# Navigator_Connectors.net
KiCad netlist of a schematic drawn in Altium Designer
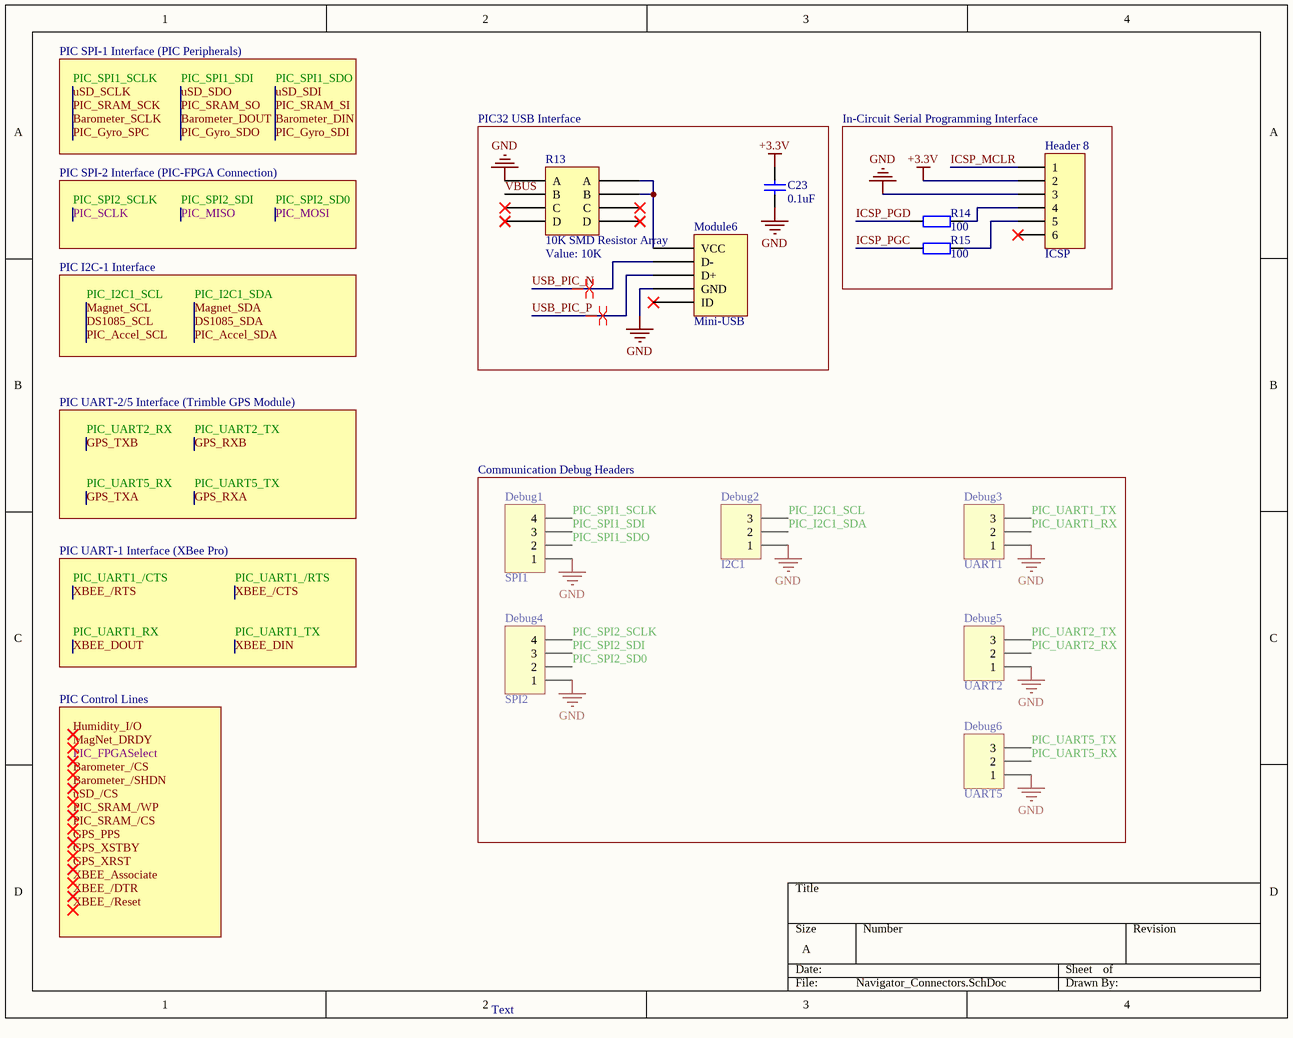
[diagram p0: Navigator_Connectors.SchDoc]

(export (version "E")
  (design (tool "Eeschema 10.0.6"))
  (components
    (comp (ref "C23")
      (value "0.1uF")
      (footprint "SMD 1206")
      (description "Capacitor")
      (fields (field (name "Comment") "0.1uF SMD 1206"))
      (libsource (lib "Miscellaneous Devices") (part "Cap"))
    )
    (comp (ref "Debug1")
      (value "SPI1")
      (footprint "HDR1X4")
      (description "Header, 4-Pin")
      (fields (field (name "PUBLISHER") "Altium Limited"))
      (libsource (lib "Miscellaneous Connectors") (part "Header 4"))
    )
    (comp (ref "Debug2")
      (value "I2C1")
      (footprint "HDR1X3")
      (description "Header, 3-Pin")
      (fields (field (name "PUBLISHER") "Altium Limited"))
      (libsource (lib "Miscellaneous Connectors") (part "Header 3"))
    )
    (comp (ref "Debug3")
      (value "UART1")
      (footprint "HDR1X3")
      (description "Header, 3-Pin")
      (fields (field (name "PUBLISHER") "Altium Limited"))
      (libsource (lib "Miscellaneous Connectors") (part "Header 3"))
    )
    (comp (ref "Debug4")
      (value "SPI2")
      (footprint "HDR1X4")
      (description "Header, 4-Pin")
      (fields (field (name "PUBLISHER") "Altium Limited"))
      (libsource (lib "Miscellaneous Connectors") (part "Header 4"))
    )
    (comp (ref "Debug5")
      (value "UART2")
      (footprint "HDR1X3")
      (description "Header, 3-Pin")
      (fields (field (name "PUBLISHER") "Altium Limited"))
      (libsource (lib "Miscellaneous Connectors") (part "Header 3"))
    )
    (comp (ref "Debug6")
      (value "UART5")
      (footprint "HDR1X3")
      (description "Header, 3-Pin")
      (fields (field (name "PUBLISHER") "Altium Limited"))
      (libsource (lib "Miscellaneous Connectors") (part "Header 3"))
    )
    (comp (ref "Header 8")
      (value "ICSP")
      (footprint "HDR1X6H")
      (description "Header, 6-Pin")
      (fields (field (name "PUBLISHER") "Altium Limited"))
      (libsource (lib "Miscellaneous Connectors") (part "Header 6"))
    )
    (comp (ref "Module6")
      (value "Mini-USB")
      (footprint "Mini B USB Connector")
      (libsource (lib "Ad-Flier_Parts") (part "Mini USB Connector"))
    )
    (comp (ref "R13")
      (value "10K SMD Resistor Array")
      (footprint "Resistor Array YC164")
      (description "4-Count Resistor Array")
      (fields (field (name "ALTIUM_VALUE") "10K"))
      (libsource (lib "Ad-Flier_Parts") (part "SMD Resistor Array"))
    )
    (comp (ref "R14")
      (value "100")
      (footprint "SMD 0805")
      (description "Resistor")
      (fields (field (name "Comment") "100 SMD 0805"))
      (libsource (lib "Miscellaneous Devices") (part "Res2"))
    )
    (comp (ref "R15")
      (value "100")
      (footprint "SMD 0805")
      (description "Resistor")
      (fields (field (name "Comment") "100 SMD 0805"))
      (libsource (lib "Miscellaneous Devices") (part "Res2"))
    )
  )
  (nets
    (net (code "1") (name "+3.3V") (class "Default")
      (node (ref "C23") (pin "2") (pinfunction "2_2") (pintype "passive"))
      (node (ref "Header 8") (pin "2") (pinfunction "2_2") (pintype "passive"))
    )
    (net (code "2") (name "/Barometer_DIN") (class "Default")
      (node (ref "Debug1") (pin "2") (pinfunction "2_2") (pintype "passive"))
    )
    (net (code "3") (name "/Barometer_DOUT") (class "Default")
      (node (ref "Debug1") (pin "3") (pinfunction "3_3") (pintype "passive"))
    )
    (net (code "4") (name "/Barometer_SCLK") (class "Default")
      (node (ref "Debug1") (pin "4") (pinfunction "4_4") (pintype "passive"))
    )
    (net (code "7") (name "/DS1085_SCL") (class "Default")
      (node (ref "Debug2") (pin "3") (pinfunction "3_3") (pintype "passive"))
    )
    (net (code "8") (name "/DS1085_SDA") (class "Default")
      (node (ref "Debug2") (pin "2") (pinfunction "2_2") (pintype "passive"))
    )
    (net (code "10") (name "/GPS_RXA") (class "Default")
      (node (ref "Debug6") (pin "3") (pinfunction "3_3") (pintype "passive"))
    )
    (net (code "11") (name "/GPS_RXB") (class "Default")
      (node (ref "Debug5") (pin "3") (pinfunction "3_3") (pintype "passive"))
    )
    (net (code "12") (name "/GPS_TXA") (class "Default")
      (node (ref "Debug6") (pin "2") (pinfunction "2_2") (pintype "passive"))
    )
    (net (code "13") (name "/GPS_TXB") (class "Default")
      (node (ref "Debug5") (pin "2") (pinfunction "2_2") (pintype "passive"))
    )
    (net (code "17") (name "/ICSP_MCLR") (class "Default")
      (node (ref "Header 8") (pin "1") (pinfunction "1_1") (pintype "passive"))
    )
    (net (code "18") (name "/ICSP_PGC") (class "Default")
      (node (ref "R15") (pin "2") (pinfunction "2_2") (pintype "passive"))
    )
    (net (code "19") (name "/ICSP_PGD") (class "Default")
      (node (ref "R14") (pin "2") (pinfunction "2_2") (pintype "passive"))
    )
    (net (code "22") (name "/PIC_MISO") (class "Default")
      (node (ref "Debug4") (pin "3") (pinfunction "3_3") (pintype "passive"))
    )
    (net (code "23") (name "/PIC_MOSI") (class "Default")
      (node (ref "Debug4") (pin "2") (pinfunction "2_2") (pintype "passive"))
    )
    (net (code "24") (name "/PIC_SCLK") (class "Default")
      (node (ref "Debug4") (pin "4") (pinfunction "4_4") (pintype "passive"))
    )
    (net (code "27") (name "/PIC_UART1_RX") (class "Default")
      (node (ref "Debug3") (pin "2") (pinfunction "2_2") (pintype "passive"))
    )
    (net (code "28") (name "/PIC_UART1_TX") (class "Default")
      (node (ref "Debug3") (pin "3") (pinfunction "3_3") (pintype "passive"))
    )
    (net (code "31") (name "/USB_PIC_N") (class "Default")
      (node (ref "Module6") (pin "3") (pinfunction "D-_3") (pintype "passive"))
    )
    (net (code "32") (name "/USB_PIC_P") (class "Default")
      (node (ref "Module6") (pin "2") (pinfunction "D+_2") (pintype "passive"))
    )
    (net (code "33") (name "/VBUS") (class "Default")
      (node (ref "R13") (pin "6") (pinfunction "B_6") (pintype "passive"))
    )
    (net (code "38") (name "GND") (class "Default")
      (node (ref "C23") (pin "1") (pinfunction "1_1") (pintype "passive"))
      (node (ref "Debug1") (pin "1") (pinfunction "1_1") (pintype "passive"))
      (node (ref "Debug2") (pin "1") (pinfunction "1_1") (pintype "passive"))
      (node (ref "Debug3") (pin "1") (pinfunction "1_1") (pintype "passive"))
      (node (ref "Debug4") (pin "1") (pinfunction "1_1") (pintype "passive"))
      (node (ref "Debug5") (pin "1") (pinfunction "1_1") (pintype "passive"))
      (node (ref "Debug6") (pin "1") (pinfunction "1_1") (pintype "passive"))
      (node (ref "Header 8") (pin "3") (pinfunction "3_3") (pintype "passive"))
      (node (ref "Module6") (pin "0") (pinfunction "GND_0") (pintype "passive"))
      (node (ref "R13") (pin "5") (pinfunction "A_5") (pintype "passive"))
    )
    (net (code "39") (name "Net-(Header 8-Pad4)") (class "Default")
      (node (ref "Header 8") (pin "4") (pinfunction "4_4") (pintype "passive"))
      (node (ref "R14") (pin "1") (pinfunction "1_1") (pintype "passive"))
    )
    (net (code "40") (name "Net-(Header 8-Pad5)") (class "Default")
      (node (ref "Header 8") (pin "5") (pinfunction "5_5") (pintype "passive"))
      (node (ref "R15") (pin "1") (pinfunction "1_1") (pintype "passive"))
    )
    (net (code "41") (name "Net-(Module6-VCC)") (class "Default")
      (node (ref "Module6") (pin "4") (pinfunction "VCC_4") (pintype "passive"))
      (node (ref "R13") (pin "1") (pinfunction "A_1") (pintype "passive"))
      (node (ref "R13") (pin "2") (pinfunction "B_2") (pintype "passive"))
    )
    (net (code "42") (name "unconnected-(Header 8-Pad6)") (class "Default")
      (node (ref "Header 8") (pin "6") (pinfunction "6_6") (pintype "passive+no_connect"))
    )
    (net (code "43") (name "unconnected-(Module6-ID-Pad1)") (class "Default")
      (node (ref "Module6") (pin "1") (pinfunction "ID_1") (pintype "passive+no_connect"))
    )
    (net (code "44") (name "unconnected-(R13-C-Pad3)") (class "Default")
      (node (ref "R13") (pin "3") (pinfunction "C_3") (pintype "passive+no_connect"))
    )
    (net (code "45") (name "unconnected-(R13-C-Pad7)") (class "Default")
      (node (ref "R13") (pin "7") (pinfunction "C_7") (pintype "passive+no_connect"))
    )
    (net (code "46") (name "unconnected-(R13-D-Pad4)") (class "Default")
      (node (ref "R13") (pin "4") (pinfunction "D_4") (pintype "passive+no_connect"))
    )
    (net (code "47") (name "unconnected-(R13-D-Pad8)") (class "Default")
      (node (ref "R13") (pin "8") (pinfunction "D_8") (pintype "passive+no_connect"))
    )
  )
)
